# ai_breakout_microusb.net
KiCad netlist of a schematic drawn in EAGLE
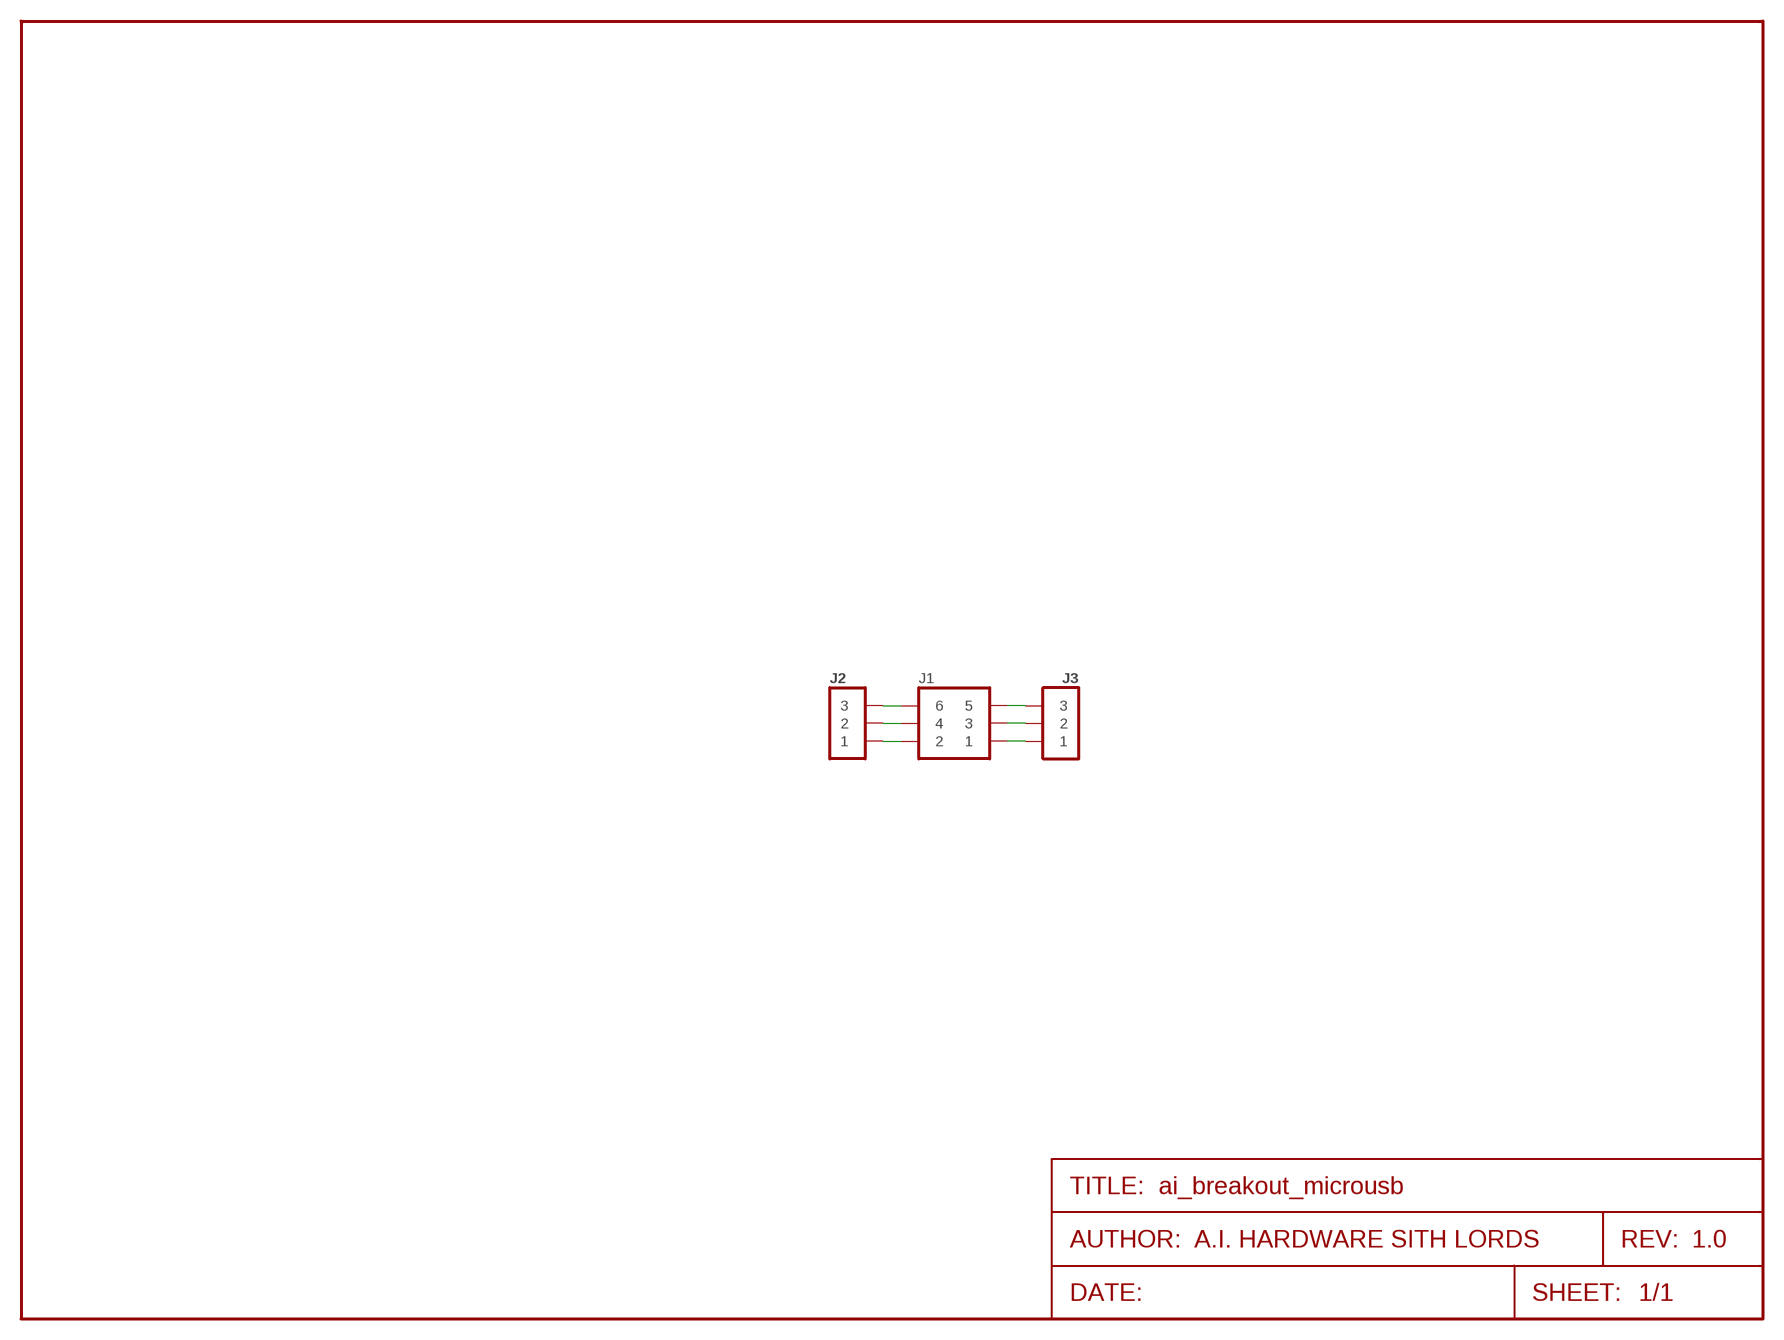
[diagram p0: schematic, sheet 1]

(export (version "E")
  (design (tool "Eeschema 10.0.6"))
  (components
    (comp (ref "J1")
      (value "2X03")
      (footprint "eagle-import:2X03")
      (libsource (lib "eagle-import") (part "2X03"))
    )
    (comp (ref "J2")
      (value "1X03NOFIRST")
      (footprint "eagle-import:1X03-NOFIRST")
      (libsource (lib "eagle-import") (part "1X03NOFIRST"))
    )
    (comp (ref "J3")
      (value "1X03")
      (footprint "eagle-import:1X03")
      (libsource (lib "eagle-import") (part "1X03"))
    )
  )
  (nets
    (net (code "1") (name "Net-(J1-Pad1)") (class "Default")
      (node (ref "J1") (pin "1") (pinfunction "1_1") (pintype "bidirectional"))
      (node (ref "J3") (pin "1") (pinfunction "1_1") (pintype "bidirectional"))
    )
    (net (code "2") (name "Net-(J1-Pad2)") (class "Default")
      (node (ref "J1") (pin "2") (pinfunction "2_2") (pintype "bidirectional"))
      (node (ref "J2") (pin "1") (pinfunction "1_1") (pintype "bidirectional"))
    )
    (net (code "3") (name "Net-(J1-Pad3)") (class "Default")
      (node (ref "J1") (pin "3") (pinfunction "3_3") (pintype "bidirectional"))
      (node (ref "J3") (pin "2") (pinfunction "2_2") (pintype "bidirectional"))
    )
    (net (code "4") (name "Net-(J1-Pad4)") (class "Default")
      (node (ref "J1") (pin "4") (pinfunction "4_4") (pintype "bidirectional"))
      (node (ref "J2") (pin "2") (pinfunction "2_2") (pintype "bidirectional"))
    )
    (net (code "5") (name "Net-(J1-Pad5)") (class "Default")
      (node (ref "J1") (pin "5") (pinfunction "5_5") (pintype "bidirectional"))
      (node (ref "J3") (pin "3") (pinfunction "3_3") (pintype "bidirectional"))
    )
    (net (code "6") (name "Net-(J1-Pad6)") (class "Default")
      (node (ref "J1") (pin "6") (pinfunction "6_6") (pintype "bidirectional"))
      (node (ref "J2") (pin "3") (pinfunction "3_3") (pintype "bidirectional"))
    )
  )
)
